# PA_Alim.net
KiCad netlist of a schematic drawn in Altium Designer
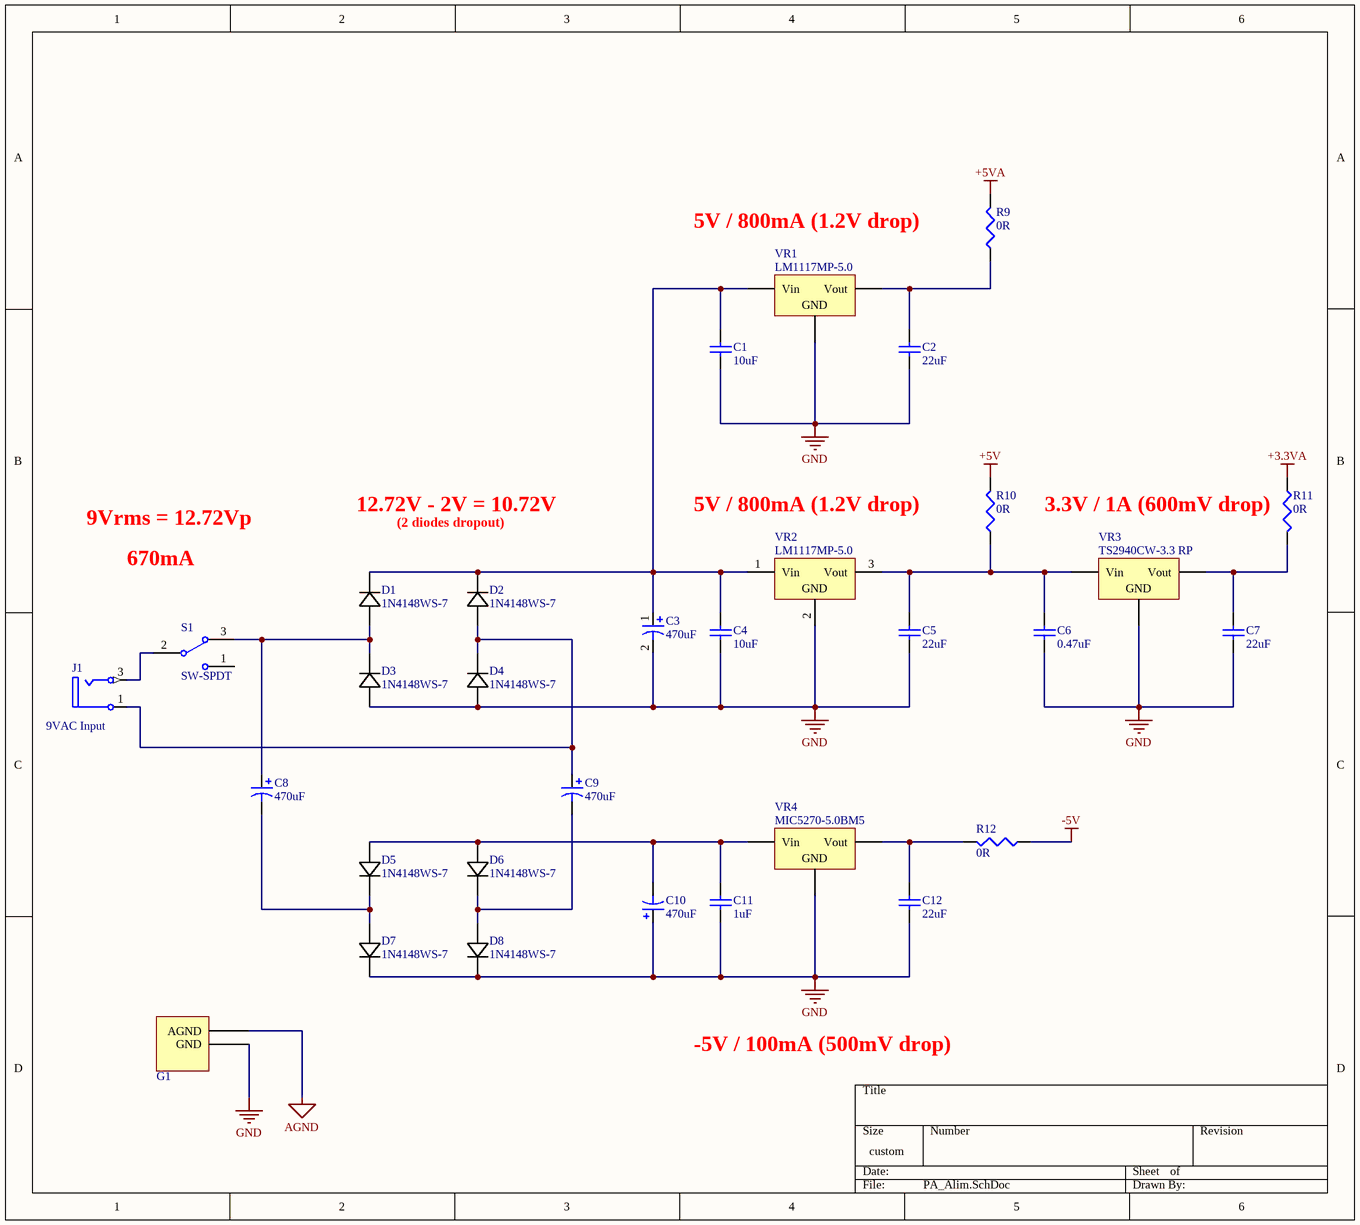
[diagram p0: PA_Alim.SchDoc]

(export (version "E")
  (design (tool "Eeschema 10.0.6"))
  (components
    (comp (ref "C1")
      (value "10uF")
      (footprint "CAPC1608X08")
      (description "Capacitor (Semiconductor SIM Model)")
      (libsource (lib "Michel") (part "Cap Semi"))
    )
    (comp (ref "C2")
      (value "22uF")
      (footprint "CAPC1608X08")
      (description "Capacitor (Semiconductor SIM Model)")
      (libsource (lib "Michel") (part "Cap Semi"))
    )
    (comp (ref "C3")
      (value "470uF")
      (footprint "CAPC100100X102")
      (description "Polarized Capacitor (Radial)")
      (libsource (lib "Michel") (part "Cap Pol1"))
    )
    (comp (ref "C4")
      (value "10uF")
      (footprint "CAPC1608X08")
      (description "Capacitor (Semiconductor SIM Model)")
      (libsource (lib "Michel") (part "Cap Semi"))
    )
    (comp (ref "C5")
      (value "22uF")
      (footprint "CAPC1608X08")
      (description "Capacitor (Semiconductor SIM Model)")
      (libsource (lib "Michel") (part "Cap Semi"))
    )
    (comp (ref "C6")
      (value "0.47uF")
      (footprint "CAPC1608X08")
      (description "Capacitor (Semiconductor SIM Model)")
      (libsource (lib "Michel") (part "Cap Semi"))
    )
    (comp (ref "C7")
      (value "22uF")
      (footprint "CAPC1608X08")
      (description "Capacitor (Semiconductor SIM Model)")
      (libsource (lib "Michel") (part "Cap Semi"))
    )
    (comp (ref "C8")
      (value "470uF")
      (footprint "CAPC100100X102")
      (description "Polarized Capacitor (Radial)")
      (libsource (lib "") (part "Cap Pol1_1"))
    )
    (comp (ref "C9")
      (value "470uF")
      (footprint "CAPC100100X102")
      (description "Polarized Capacitor (Radial)")
      (libsource (lib "") (part "Cap Pol1_1"))
    )
    (comp (ref "C10")
      (value "470uF")
      (footprint "CAPC100100X102")
      (description "Polarized Capacitor (Radial)")
      (libsource (lib "") (part "Cap Pol1_1"))
    )
    (comp (ref "C11")
      (value "1uF")
      (footprint "CAPC1608X08")
      (description "Capacitor")
      (libsource (lib "Michel") (part "Cap Semi"))
    )
    (comp (ref "C12")
      (value "22uF")
      (footprint "CAPC1608X08")
      (description "Capacitor (Semiconductor SIM Model)")
      (libsource (lib "Michel") (part "Cap Semi"))
    )
    (comp (ref "D1")
      (value "1N4148WS-7")
      (footprint "SOD323-M")
      (description "Diode signaux faibles")
      (libsource (lib "Michel") (part "1N4148WS-7"))
    )
    (comp (ref "D2")
      (value "1N4148WS-7")
      (footprint "SOD323-M")
      (description "Diode signaux faibles")
      (libsource (lib "Michel") (part "1N4148WS-7"))
    )
    (comp (ref "D3")
      (value "1N4148WS-7")
      (footprint "SOD323-M")
      (description "Diode signaux faibles")
      (libsource (lib "Michel") (part "1N4148WS-7"))
    )
    (comp (ref "D4")
      (value "1N4148WS-7")
      (footprint "SOD323-M")
      (description "Diode signaux faibles")
      (libsource (lib "Michel") (part "1N4148WS-7"))
    )
    (comp (ref "D5")
      (value "1N4148WS-7")
      (footprint "SOD323-M")
      (description "Diode signaux faibles")
      (libsource (lib "Michel") (part "1N4148WS-7"))
    )
    (comp (ref "D6")
      (value "1N4148WS-7")
      (footprint "SOD323-M")
      (description "Diode signaux faibles")
      (libsource (lib "Michel") (part "1N4148WS-7"))
    )
    (comp (ref "D7")
      (value "1N4148WS-7")
      (footprint "SOD323-M")
      (description "Diode signaux faibles")
      (libsource (lib "Michel") (part "1N4148WS-7"))
    )
    (comp (ref "D8")
      (value "1N4148WS-7")
      (footprint "SOD323-M")
      (description "Diode signaux faibles")
      (libsource (lib "Michel") (part "1N4148WS-7"))
    )
    (comp (ref "G1")
      (value "Ground Connector")
      (footprint "GND")
      (description "Ground Ultime")
      (libsource (lib "Michel") (part "GND"))
    )
    (comp (ref "J1")
      (value "9VAC Input")
      (footprint "CLIFF ELECTRONIC COMPONENTS_FC681465P")
      (description "Jack Socket Thru-Hole Vertical 2-Conductor Open Circuit")
      (libsource (lib "Michel") (part "Phonejack2"))
    )
    (comp (ref "R9")
      (value "0R")
      (footprint "RESC1608X05")
      (description "Resistor")
      (libsource (lib "Michel") (part "Res3"))
    )
    (comp (ref "R10")
      (value "0R")
      (footprint "RESC1608X05")
      (description "Resistor")
      (libsource (lib "Michel") (part "Res3"))
    )
    (comp (ref "R11")
      (value "0R")
      (footprint "RESC1608X05")
      (description "Resistor")
      (libsource (lib "Michel") (part "Res3"))
    )
    (comp (ref "R12")
      (value "0R")
      (footprint "RESC1608X05")
      (description "Resistor")
      (libsource (lib "Michel") (part "Res3"))
    )
    (comp (ref "S1")
      (value "SW-SPDT")
      (footprint "C&K_TS01ABE")
      (description "SPDT Subminiature Toggle Switch, Right Angle Mounting, Vertical Actuation")
      (libsource (lib "Michel") (part "SW-SPDT"))
    )
    (comp (ref "VR1")
      (value "LM1117MP-5.0")
      (footprint "MP04A")
      (description "Voltage Regulator")
      (libsource (lib "Michel") (part "Volt Reg"))
    )
    (comp (ref "VR2")
      (value "LM1117MP-5.0")
      (footprint "MP04A")
      (description "Voltage Regulator")
      (libsource (lib "") (part "Volt Reg_1"))
    )
    (comp (ref "VR3")
      (value "TS2940CW-3.3 RP")
      (footprint "SOT230P715X180-4N")
      (description "Voltage Regulator")
      (libsource (lib "Michel") (part "Volt Reg"))
    )
    (comp (ref "VR4")
      (value "MIC5270-5.0BM5")
      (footprint "SOT95P280X130-5N")
      (description "Voltage Regulator")
      (libsource (lib "Michel") (part "Volt Reg"))
    )
  )
  (nets
    (net (code "1") (name "+3.3VA") (class "Default")
      (node (ref "R11") (pin "1") (pinfunction "1_1") (pintype "passive"))
    )
    (net (code "2") (name "+5V") (class "Default")
      (node (ref "R10") (pin "2") (pinfunction "2_2") (pintype "passive"))
    )
    (net (code "3") (name "+5VA") (class "Default")
      (node (ref "R9") (pin "2") (pinfunction "2_2") (pintype "passive"))
    )
    (net (code "4") (name "-5V") (class "Default")
      (node (ref "R12") (pin "1") (pinfunction "1_1") (pintype "passive"))
    )
    (net (code "5") (name "AGND") (class "Default")
      (node (ref "G1") (pin "1") (pinfunction "AGND_1") (pintype "passive"))
    )
    (net (code "6") (name "GND") (class "Default")
      (node (ref "C1") (pin "1") (pinfunction "1_1") (pintype "passive"))
      (node (ref "C10") (pin "1") (pinfunction "1_1") (pintype "passive"))
      (node (ref "C11") (pin "1") (pinfunction "1_1") (pintype "passive"))
      (node (ref "C12") (pin "1") (pinfunction "1_1") (pintype "passive"))
      (node (ref "C2") (pin "1") (pinfunction "1_1") (pintype "passive"))
      (node (ref "C3") (pin "2") (pinfunction "2_2") (pintype "passive"))
      (node (ref "C4") (pin "1") (pinfunction "1_1") (pintype "passive"))
      (node (ref "C5") (pin "1") (pinfunction "1_1") (pintype "passive"))
      (node (ref "C6") (pin "1") (pinfunction "1_1") (pintype "passive"))
      (node (ref "C7") (pin "1") (pinfunction "1_1") (pintype "passive"))
      (node (ref "D3") (pin "2") (pinfunction "2_2") (pintype "passive"))
      (node (ref "D4") (pin "2") (pinfunction "2_2") (pintype "passive"))
      (node (ref "D7") (pin "1") (pinfunction "1_1") (pintype "passive"))
      (node (ref "D8") (pin "1") (pinfunction "1_1") (pintype "passive"))
      (node (ref "G1") (pin "2") (pinfunction "GND_2") (pintype "passive"))
      (node (ref "VR1") (pin "2") (pinfunction "GND_2") (pintype "passive"))
      (node (ref "VR2") (pin "2") (pinfunction "GND_2") (pintype "passive"))
      (node (ref "VR3") (pin "2") (pinfunction "GND_2") (pintype "passive"))
      (node (ref "VR4") (pin "2") (pinfunction "GND_2") (pintype "passive"))
    )
    (net (code "7") (name "Net-(C8-Pad1)") (class "Default")
      (node (ref "C8") (pin "1") (pinfunction "1_1") (pintype "passive"))
      (node (ref "D1") (pin "2") (pinfunction "2_2") (pintype "passive"))
      (node (ref "D3") (pin "1") (pinfunction "1_1") (pintype "passive"))
      (node (ref "S1") (pin "3") (pinfunction "3_3") (pintype "passive"))
    )
    (net (code "8") (name "Net-(C8-Pad2)") (class "Default")
      (node (ref "C8") (pin "2") (pinfunction "2_2") (pintype "passive"))
      (node (ref "D5") (pin "1") (pinfunction "1_1") (pintype "passive"))
      (node (ref "D7") (pin "2") (pinfunction "2_2") (pintype "passive"))
    )
    (net (code "9") (name "Net-(C9-Pad2)") (class "Default")
      (node (ref "C9") (pin "2") (pinfunction "2_2") (pintype "passive"))
      (node (ref "D6") (pin "1") (pinfunction "1_1") (pintype "passive"))
      (node (ref "D8") (pin "2") (pinfunction "2_2") (pintype "passive"))
    )
    (net (code "10") (name "Net-(J1-S)") (class "Default")
      (node (ref "C9") (pin "1") (pinfunction "1_1") (pintype "passive"))
      (node (ref "D2") (pin "2") (pinfunction "2_2") (pintype "passive"))
      (node (ref "D4") (pin "1") (pinfunction "1_1") (pintype "passive"))
      (node (ref "J1") (pin "1") (pinfunction "S_1") (pintype "power_in"))
    )
    (net (code "11") (name "Net-(J1-T)") (class "Default")
      (node (ref "J1") (pin "3") (pinfunction "T_3") (pintype "output"))
      (node (ref "S1") (pin "2") (pinfunction "2_2") (pintype "passive"))
    )
    (net (code "12") (name "Net-(VR1-Vin)") (class "Default")
      (node (ref "C1") (pin "2") (pinfunction "2_2") (pintype "passive"))
      (node (ref "C3") (pin "1") (pinfunction "1_1") (pintype "passive"))
      (node (ref "C4") (pin "2") (pinfunction "2_2") (pintype "passive"))
      (node (ref "D1") (pin "1") (pinfunction "1_1") (pintype "passive"))
      (node (ref "D2") (pin "1") (pinfunction "1_1") (pintype "passive"))
      (node (ref "VR1") (pin "1") (pinfunction "Vin_1") (pintype "passive"))
      (node (ref "VR2") (pin "1") (pinfunction "Vin_1") (pintype "passive"))
    )
    (net (code "13") (name "Net-(VR1-Vout)") (class "Default")
      (node (ref "C2") (pin "2") (pinfunction "2_2") (pintype "passive"))
      (node (ref "R9") (pin "1") (pinfunction "1_1") (pintype "passive"))
      (node (ref "VR1") (pin "3") (pinfunction "Vout_3") (pintype "passive"))
    )
    (net (code "14") (name "Net-(VR2-Vout)") (class "Default")
      (node (ref "C5") (pin "2") (pinfunction "2_2") (pintype "passive"))
      (node (ref "C6") (pin "2") (pinfunction "2_2") (pintype "passive"))
      (node (ref "R10") (pin "1") (pinfunction "1_1") (pintype "passive"))
      (node (ref "VR2") (pin "3") (pinfunction "Vout_3") (pintype "passive"))
      (node (ref "VR3") (pin "1") (pinfunction "Vin_1") (pintype "passive"))
    )
    (net (code "15") (name "Net-(VR3-Vout)") (class "Default")
      (node (ref "C7") (pin "2") (pinfunction "2_2") (pintype "passive"))
      (node (ref "R11") (pin "2") (pinfunction "2_2") (pintype "passive"))
      (node (ref "VR3") (pin "3") (pinfunction "Vout_3") (pintype "passive"))
    )
    (net (code "16") (name "Net-(VR4-Vin)") (class "Default")
      (node (ref "C10") (pin "2") (pinfunction "2_2") (pintype "passive"))
      (node (ref "C11") (pin "2") (pinfunction "2_2") (pintype "passive"))
      (node (ref "D5") (pin "2") (pinfunction "2_2") (pintype "passive"))
      (node (ref "D6") (pin "2") (pinfunction "2_2") (pintype "passive"))
      (node (ref "VR4") (pin "1") (pinfunction "Vin_1") (pintype "passive"))
    )
    (net (code "17") (name "Net-(VR4-Vout)") (class "Default")
      (node (ref "C12") (pin "2") (pinfunction "2_2") (pintype "passive"))
      (node (ref "R12") (pin "2") (pinfunction "2_2") (pintype "passive"))
      (node (ref "VR4") (pin "3") (pinfunction "Vout_3") (pintype "passive"))
    )
    (net (code "18") (name "unconnected-(S1-Pad1)") (class "Default")
      (node (ref "S1") (pin "1") (pinfunction "1_1") (pintype "passive"))
    )
  )
)
